# ArduinoUnoShield.net
KiCad netlist of a schematic drawn in Altium Designer
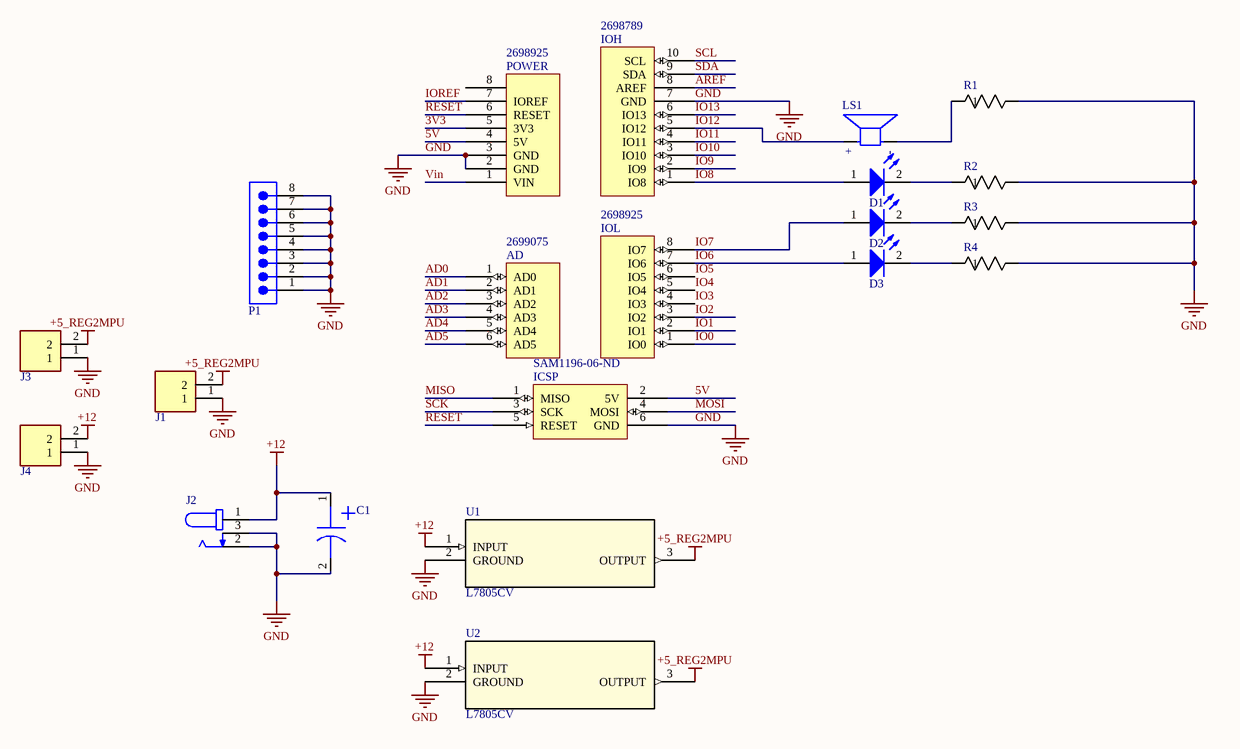
[diagram p0: ArduinoUnoShield.SchDoc]

(export (version "E")
  (design (tool "Eeschema 10.0.6"))
  (components
    (comp (ref "AD")
      (value "AD")
      (footprint "Header:Header 6x1 8.5mm")
      (fields (field (name "SUPPLIER PART NUMBER 4") "2699075"))
      (libsource (lib "Header") (part "AD"))
    )
    (comp (ref "C1")
      (value "ESK475M035AC3AA")
      (footprint "CAP THT ELECTROLYTIC")
      (description "CAP ALUM 4.7UF 20% 35V RADIAL TH")
      (libsource (lib "M_ElAbd") (part "ESK475M035AC3AA"))
    )
    (comp (ref "D1")
      (value "Blue, 3.2V, 40°")
      (footprint "LED THROUGH HOLE")
      (description "WL-TMRC Mono-color Round Color, THT, D5.9 x H8.7mm, Blue, 3.2V, 40°")
      (fields
        (field (name "MANUFACTURER PART NUMBER") "151051BS04000")
        (field (name "MANUFACTURER") "Wurth Elektronik")
      )
      (libsource (lib "M_ElAbd") (part "151051BS04000"))
    )
    (comp (ref "D2")
      (value "Blue, 3.2V, 40°")
      (footprint "LED THROUGH HOLE")
      (description "WL-TMRC Mono-color Round Color, THT, D5.9 x H8.7mm, Blue, 3.2V, 40°")
      (fields
        (field (name "MANUFACTURER PART NUMBER") "151051BS04000")
        (field (name "MANUFACTURER") "Wurth Elektronik")
      )
      (libsource (lib "M_ElAbd") (part "151051BS04000"))
    )
    (comp (ref "D3")
      (value "Blue, 3.2V, 40°")
      (footprint "LED THROUGH HOLE")
      (description "WL-TMRC Mono-color Round Color, THT, D5.9 x H8.7mm, Blue, 3.2V, 40°")
      (fields
        (field (name "MANUFACTURER PART NUMBER") "151051BS04000")
        (field (name "MANUFACTURER") "Wurth Elektronik")
      )
      (libsource (lib "M_ElAbd") (part "151051BS04000"))
    )
    (comp (ref "ICSP")
      (value "ICSP")
      (footprint "ICSP")
      (fields (field (name "SUPPLIER PART NUMBER 5") "SAM1196-06-ND"))
      (libsource (lib "Header") (part "ICSP"))
    )
    (comp (ref "IOH")
      (value "IOH")
      (footprint "Header:Header 10x1 8.5mm")
      (fields (field (name "SUPPLIER PART NUMBER 3") "2698789"))
      (libsource (lib "Header") (part "IOH"))
    )
    (comp (ref "IOL")
      (value "IOL")
      (footprint "Header 8x1 8.5mm")
      (fields (field (name "SUPPLIER PART NUMBER 4") "2698925"))
      (libsource (lib "Header") (part "IOL"))
    )
    (comp (ref "J1")
      (value "282836-2")
      (footprint "TE_282836-2")
      (fields (field (name "MF") "TE Connectivity"))
      (libsource (lib "M_ElAbd") (part "282836-2"))
    )
    (comp (ref "J2")
      (value "DCJ200-10-A-XX-K_REVA")
      (footprint "DC POWER JACK")
      (description "Power Barrel Connector Jack 2.05mm ID (0.081), 5.50mm OD (0.217) Through Hole, Right Angle")
      (fields (field (name "MF") "Global Connector Technology") (field (name "MP") "DCJ200-10-A-K1-K"))
      (libsource (lib "M_ElAbd") (part "DCJ200-10-A-XX-K_REVA"))
    )
    (comp (ref "J3")
      (value "282836-2")
      (footprint "TE_282836-2")
      (fields (field (name "MF") "TE Connectivity"))
      (libsource (lib "M_ElAbd") (part "282836-2"))
    )
    (comp (ref "J4")
      (value "282836-2")
      (footprint "TE_282836-2")
      (fields (field (name "MF") "TE Connectivity"))
      (libsource (lib "M_ElAbd") (part "282836-2"))
    )
    (comp (ref "LS1")
      (value "AT-1224-TWT-5V-2-R")
      (footprint "BUZZER")
      (libsource (lib "M_ElAbd") (part "AT-1224-TWT-5V-2-R"))
    )
    (comp (ref "P1")
      (value "61300811121")
      (footprint "8 PIN HEADER")
      (description "WR-PHD Pin Header, THT, Vertical, pitch 2.54mm, 1 Row, 8P")
      (fields (field (name "MANUFACTURER") "Wurth Elektronik"))
      (libsource (lib "M_ElAbd") (part "61300811121"))
    )
    (comp (ref "POWER")
      (value "POWER_UNO")
      (footprint "Header 8x1 8.5mm")
      (fields (field (name "SUPPLIER PART NUMBER 4") "2698925"))
      (libsource (lib "Header") (part "POWER_UNO"))
    )
    (comp (ref "R1")
      (value "RNMF14FTC200R")
      (footprint "RESISTOR THROUGH HOLE")
      (description "200 Ohms ±1% 0.25W, 1/4W Through Hole Resistor Axial Flame Retardant Coating, Safety Metal Film")
      (libsource (lib "M_ElAbd") (part "RNMF14FTC200R"))
    )
    (comp (ref "R2")
      (value "RNMF14FTC200R")
      (footprint "RESISTOR THROUGH HOLE")
      (description "200 Ohms ±1% 0.25W, 1/4W Through Hole Resistor Axial Flame Retardant Coating, Safety Metal Film")
      (libsource (lib "M_ElAbd") (part "RNMF14FTC200R"))
    )
    (comp (ref "R3")
      (value "RNMF14FTC200R")
      (footprint "RESISTOR THROUGH HOLE")
      (description "200 Ohms ±1% 0.25W, 1/4W Through Hole Resistor Axial Flame Retardant Coating, Safety Metal Film")
      (libsource (lib "M_ElAbd") (part "RNMF14FTC200R"))
    )
    (comp (ref "R4")
      (value "RNMF14FTC200R")
      (footprint "RESISTOR THROUGH HOLE")
      (description "200 Ohms ±1% 0.25W, 1/4W Through Hole Resistor Axial Flame Retardant Coating, Safety Metal Film")
      (libsource (lib "M_ElAbd") (part "RNMF14FTC200R"))
    )
    (comp (ref "U1")
      (value "L7805CV")
      (footprint "7805 REG")
      (description "Linear Voltage Regulator IC Positive Fixed 1 Output 1.5A TO-220")
      (libsource (lib "M_ElAbd") (part "L7805CV"))
    )
    (comp (ref "U2")
      (value "L7805CV")
      (footprint "7805 REG")
      (description "Linear Voltage Regulator IC Positive Fixed 1 Output 1.5A TO-220")
      (libsource (lib "M_ElAbd") (part "L7805CV"))
    )
  )
  (nets
    (net (code "1") (name "+5_REG2MPU") (class "Default")
      (node (ref "J1") (pin "2") (pinfunction "2_2") (pintype "passive"))
      (node (ref "J3") (pin "2") (pinfunction "2_2") (pintype "passive"))
      (node (ref "U1") (pin "3") (pinfunction "OUTPUT_3") (pintype "output"))
      (node (ref "U2") (pin "3") (pinfunction "OUTPUT_3") (pintype "output"))
    )
    (net (code "2") (name "+12") (class "Default")
      (node (ref "C1") (pin "1") (pinfunction "1_1") (pintype "passive"))
      (node (ref "J2") (pin "1") (pinfunction "1_1") (pintype "passive"))
      (node (ref "J4") (pin "2") (pinfunction "2_2") (pintype "passive"))
      (node (ref "U1") (pin "1") (pinfunction "INPUT_1") (pintype "input"))
      (node (ref "U2") (pin "1") (pinfunction "INPUT_1") (pintype "input"))
    )
    (net (code "3") (name "/3V3") (class "Default")
      (node (ref "POWER") (pin "5") (pinfunction "3V3_5") (pintype "power_in"))
    )
    (net (code "4") (name "/5V") (class "Default")
      (node (ref "ICSP") (pin "2") (pinfunction "5V_2") (pintype "power_in"))
      (node (ref "POWER") (pin "4") (pinfunction "5V_4") (pintype "power_in"))
    )
    (net (code "6") (name "/AD0") (class "Default")
      (node (ref "AD") (pin "1") (pinfunction "AD0_1") (pintype "bidirectional"))
    )
    (net (code "7") (name "/AD1") (class "Default")
      (node (ref "AD") (pin "2") (pinfunction "AD1_2") (pintype "bidirectional"))
    )
    (net (code "8") (name "/AD2") (class "Default")
      (node (ref "AD") (pin "3") (pinfunction "AD2_3") (pintype "bidirectional"))
    )
    (net (code "9") (name "/AD3") (class "Default")
      (node (ref "AD") (pin "4") (pinfunction "AD3_4") (pintype "bidirectional"))
    )
    (net (code "10") (name "/AD4") (class "Default")
      (node (ref "AD") (pin "5") (pinfunction "AD4_5") (pintype "bidirectional"))
    )
    (net (code "11") (name "/AD5") (class "Default")
      (node (ref "AD") (pin "6") (pinfunction "AD5_6") (pintype "bidirectional"))
    )
    (net (code "12") (name "/AREF") (class "Default")
      (node (ref "IOH") (pin "8") (pinfunction "AREF_8") (pintype "passive"))
    )
    (net (code "13") (name "/IO0") (class "Default")
      (node (ref "IOL") (pin "1") (pinfunction "IO0_1") (pintype "bidirectional"))
    )
    (net (code "14") (name "/IO1") (class "Default")
      (node (ref "IOL") (pin "2") (pinfunction "IO1_2") (pintype "bidirectional"))
    )
    (net (code "15") (name "/IO2") (class "Default")
      (node (ref "IOL") (pin "3") (pinfunction "IO2_3") (pintype "bidirectional"))
    )
    (net (code "16") (name "/IO3") (class "Default")
      (node (ref "IOL") (pin "4") (pinfunction "IO3_4") (pintype "bidirectional"))
    )
    (net (code "17") (name "/IO4") (class "Default")
      (node (ref "IOL") (pin "5") (pinfunction "IO4_5") (pintype "bidirectional"))
    )
    (net (code "18") (name "/IO5") (class "Default")
      (node (ref "IOL") (pin "6") (pinfunction "IO5_6") (pintype "bidirectional"))
    )
    (net (code "19") (name "/IO6") (class "Default")
      (node (ref "D3") (pin "1") (pinfunction "A_1") (pintype "passive"))
      (node (ref "IOL") (pin "7") (pinfunction "IO6_7") (pintype "bidirectional"))
    )
    (net (code "20") (name "/IO7") (class "Default")
      (node (ref "D2") (pin "1") (pinfunction "A_1") (pintype "passive"))
      (node (ref "IOL") (pin "8") (pinfunction "IO7_8") (pintype "bidirectional"))
    )
    (net (code "21") (name "/IO8") (class "Default")
      (node (ref "D1") (pin "1") (pinfunction "A_1") (pintype "passive"))
      (node (ref "IOH") (pin "1") (pinfunction "IO8_1") (pintype "bidirectional"))
    )
    (net (code "22") (name "/IO9") (class "Default")
      (node (ref "IOH") (pin "2") (pinfunction "IO9_2") (pintype "bidirectional"))
    )
    (net (code "23") (name "/IO10") (class "Default")
      (node (ref "IOH") (pin "3") (pinfunction "IO10_3") (pintype "bidirectional"))
    )
    (net (code "24") (name "/IO11") (class "Default")
      (node (ref "IOH") (pin "4") (pinfunction "IO11_4") (pintype "bidirectional"))
    )
    (net (code "25") (name "/IO12") (class "Default")
      (node (ref "IOH") (pin "5") (pinfunction "IO12_5") (pintype "bidirectional"))
      (node (ref "LS1") (pin "P") (pinfunction "P_P") (pintype "passive"))
    )
    (net (code "26") (name "/IO13") (class "Default")
      (node (ref "IOH") (pin "6") (pinfunction "IO13_6") (pintype "bidirectional"))
    )
    (net (code "27") (name "/IOREF") (class "Default")
      (node (ref "POWER") (pin "7") (pinfunction "IOREF_7") (pintype "power_in"))
    )
    (net (code "28") (name "/MISO") (class "Default")
      (node (ref "ICSP") (pin "1") (pinfunction "MISO_1") (pintype "bidirectional"))
    )
    (net (code "29") (name "/MOSI") (class "Default")
      (node (ref "ICSP") (pin "4") (pinfunction "MOSI_4") (pintype "bidirectional"))
    )
    (net (code "30") (name "/RESET") (class "Default")
      (node (ref "ICSP") (pin "5") (pinfunction "RESET_5") (pintype "input"))
      (node (ref "POWER") (pin "6") (pinfunction "RESET_6") (pintype "passive"))
    )
    (net (code "31") (name "/SCK") (class "Default")
      (node (ref "ICSP") (pin "3") (pinfunction "SCK_3") (pintype "bidirectional"))
    )
    (net (code "32") (name "/SCL") (class "Default")
      (node (ref "IOH") (pin "10") (pinfunction "SCL_10") (pintype "bidirectional"))
    )
    (net (code "33") (name "/SDA") (class "Default")
      (node (ref "IOH") (pin "9") (pinfunction "SDA_9") (pintype "bidirectional"))
    )
    (net (code "34") (name "/Vin") (class "Default")
      (node (ref "POWER") (pin "1") (pinfunction "VIN_1") (pintype "power_in"))
    )
    (net (code "35") (name "GND") (class "Default")
      (node (ref "C1") (pin "2") (pinfunction "2_2") (pintype "passive"))
      (node (ref "ICSP") (pin "6") (pinfunction "GND_6") (pintype "power_in"))
      (node (ref "IOH") (pin "7") (pinfunction "GND_7") (pintype "power_in"))
      (node (ref "J1") (pin "1") (pinfunction "1_1") (pintype "passive"))
      (node (ref "J2") (pin "2") (pinfunction "2_2") (pintype "passive"))
      (node (ref "J2") (pin "3") (pinfunction "3_3") (pintype "passive"))
      (node (ref "J3") (pin "1") (pinfunction "1_1") (pintype "passive"))
      (node (ref "J4") (pin "1") (pinfunction "1_1") (pintype "passive"))
      (node (ref "P1") (pin "1") (pinfunction "1_1") (pintype "passive"))
      (node (ref "P1") (pin "2") (pinfunction "2_2") (pintype "passive"))
      (node (ref "P1") (pin "3") (pinfunction "3_3") (pintype "passive"))
      (node (ref "P1") (pin "4") (pinfunction "4_4") (pintype "passive"))
      (node (ref "P1") (pin "5") (pinfunction "5_5") (pintype "passive"))
      (node (ref "P1") (pin "6") (pinfunction "6_6") (pintype "passive"))
      (node (ref "P1") (pin "7") (pinfunction "7_7") (pintype "passive"))
      (node (ref "P1") (pin "8") (pinfunction "8_8") (pintype "passive"))
      (node (ref "POWER") (pin "2") (pinfunction "GND_2") (pintype "power_in"))
      (node (ref "POWER") (pin "3") (pinfunction "GND_3") (pintype "power_in"))
      (node (ref "R1") (pin "2") (pinfunction "2_2") (pintype "passive"))
      (node (ref "R2") (pin "2") (pinfunction "2_2") (pintype "passive"))
      (node (ref "R3") (pin "2") (pinfunction "2_2") (pintype "passive"))
      (node (ref "R4") (pin "2") (pinfunction "2_2") (pintype "passive"))
      (node (ref "U1") (pin "2") (pinfunction "GROUND_2") (pintype "power_in"))
      (node (ref "U2") (pin "2") (pinfunction "GROUND_2") (pintype "power_in"))
    )
    (net (code "36") (name "Net-(D1-K)") (class "Default")
      (node (ref "D1") (pin "2") (pinfunction "K_2") (pintype "passive"))
      (node (ref "R2") (pin "1") (pinfunction "1_1") (pintype "passive"))
    )
    (net (code "37") (name "Net-(D2-K)") (class "Default")
      (node (ref "D2") (pin "2") (pinfunction "K_2") (pintype "passive"))
      (node (ref "R3") (pin "1") (pinfunction "1_1") (pintype "passive"))
    )
    (net (code "38") (name "Net-(D3-K)") (class "Default")
      (node (ref "D3") (pin "2") (pinfunction "K_2") (pintype "passive"))
      (node (ref "R4") (pin "1") (pinfunction "1_1") (pintype "passive"))
    )
    (net (code "39") (name "Net-(LS1-PadN)") (class "Default")
      (node (ref "LS1") (pin "N") (pinfunction "N_N") (pintype "passive"))
      (node (ref "R1") (pin "1") (pinfunction "1_1") (pintype "passive"))
    )
    (net (code "40") (name "unconnected-(POWER-Pad8)") (class "Default")
      (node (ref "POWER") (pin "8") (pintype "passive"))
    )
  )
)
